# MS3-adapter.net
KiCad netlist of a schematic drawn in EAGLE
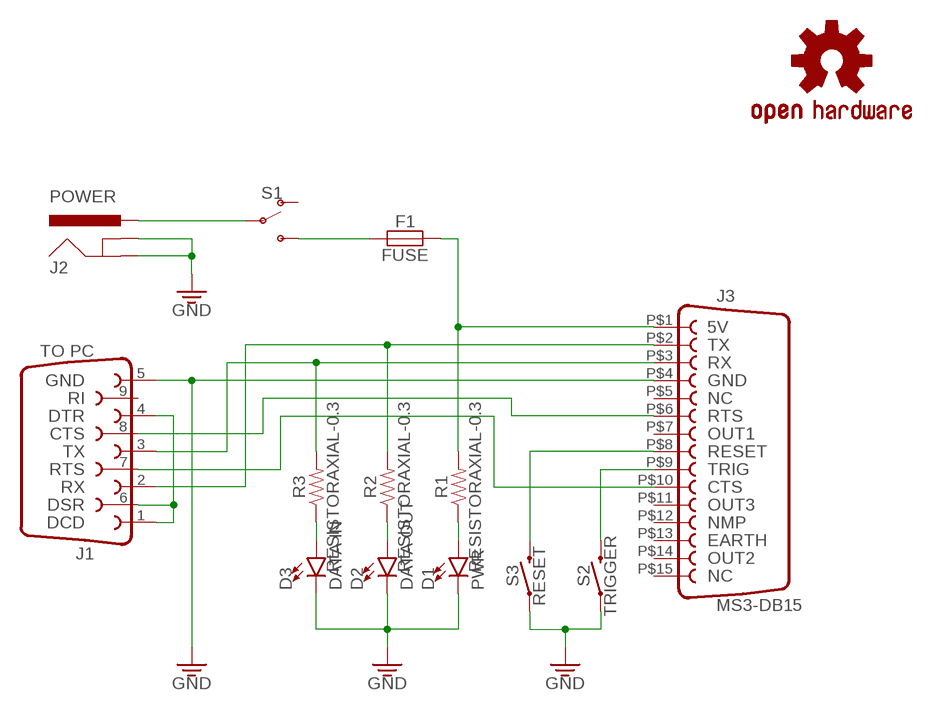
[diagram p0: schematic, sheet 1]

(export (version "E")
  (design (tool "Eeschema 10.0.6"))
  (components
    (comp (ref "D1")
      (value "PWR")
      (footprint "eagle-import:LED_5MM")
      (libsource (lib "eagle-import") (part "LED5MM"))
    )
    (comp (ref "D2")
      (value "DATA OUT")
      (footprint "eagle-import:LED_5MM")
      (libsource (lib "eagle-import") (part "LED5MM"))
    )
    (comp (ref "D3")
      (value "DATA IN")
      (footprint "eagle-import:LED_5MM")
      (libsource (lib "eagle-import") (part "LED5MM"))
    )
    (comp (ref "F1")
      (value "FUSE")
      (footprint "eagle-import:FUSEHOLDER-PAIR-5MM")
      (libsource (lib "eagle-import") (part "FUSE"))
    )
    (comp (ref "J1")
      (value "TO PC")
      (footprint "eagle-import:DB9-FEMALE")
      (libsource (lib "eagle-import") (part "DB9FEMALE"))
    )
    (comp (ref "J2")
      (value "POWER")
      (footprint "eagle-import:POWER_JACK_PTH")
      (libsource (lib "eagle-import") (part "POWER_JACK"))
    )
    (comp (ref "J3")
      (value "MS3-DB15")
      (footprint "eagle-import:DB15-MALE")
      (libsource (lib "eagle-import") (part "MS3-DB15"))
    )
    (comp (ref "LOGO1")
      (value "OSHW-LOGOS")
      (footprint "eagle-import:OSHW-LOGO-S")
      (libsource (lib "eagle-import") (part "OSHW-LOGOS"))
    )
    (comp (ref "R1")
      (value "RESISTORAXIAL-0.3")
      (footprint "eagle-import:AXIAL-0.3")
      (libsource (lib "eagle-import") (part "RESISTORAXIAL-0.3"))
    )
    (comp (ref "R2")
      (value "RESISTORAXIAL-0.3")
      (footprint "eagle-import:AXIAL-0.3")
      (libsource (lib "eagle-import") (part "RESISTORAXIAL-0.3"))
    )
    (comp (ref "R3")
      (value "RESISTORAXIAL-0.3")
      (footprint "eagle-import:AXIAL-0.3")
      (libsource (lib "eagle-import") (part "RESISTORAXIAL-0.3"))
    )
    (comp (ref "S1")
      (value "SWITCH-SPDT-PTH-11.6X4.0MM")
      (footprint "eagle-import:SWITCH_SPDT_PTH_11.6X4.0MM")
      (libsource (lib "eagle-import") (part "SWITCH-SPDT-PTH-11.6X4.0MM"))
    )
    (comp (ref "S2")
      (value "TRIGGER")
      (footprint "eagle-import:TACTILE_SWITCH_PTH_12MM")
      (libsource (lib "eagle-import") (part "MOMENTARY-SWITCH-SPST-PTH-12MM"))
    )
    (comp (ref "S3")
      (value "RESET")
      (footprint "eagle-import:TACTILE_SWITCH_PTH_12MM")
      (libsource (lib "eagle-import") (part "MOMENTARY-SWITCH-SPST-PTH-12MM"))
    )
  )
  (nets
    (net (code "1") (name "GND") (class "Default")
      (node (ref "D1") (pin "K") (pinfunction "C_K") (pintype "passive"))
      (node (ref "D2") (pin "K") (pinfunction "C_K") (pintype "passive"))
      (node (ref "D3") (pin "K") (pinfunction "C_K") (pintype "passive"))
      (node (ref "J1") (pin "5") (pinfunction "5_5") (pintype "passive"))
      (node (ref "J2") (pin "GND") (pinfunction "GND_GND") (pintype "bidirectional"))
      (node (ref "J2") (pin "GNDBREAK") (pinfunction "GNDBREAK_GNDBREAK") (pintype "bidirectional"))
      (node (ref "J3") (pin "P$4") (pinfunction "4_P$4") (pintype "passive"))
      (node (ref "S2") (pin "1") (pinfunction "1_1") (pintype "passive"))
      (node (ref "S3") (pin "1") (pinfunction "1_1") (pintype "passive"))
    )
    (net (code "2") (name "Net-(J1-Pad1)") (class "Default")
      (node (ref "J1") (pin "1") (pinfunction "1_1") (pintype "passive"))
      (node (ref "J1") (pin "4") (pinfunction "4_4") (pintype "passive"))
      (node (ref "J1") (pin "6") (pinfunction "6_6") (pintype "passive"))
    )
    (net (code "3") (name "Net-(J3-1)") (class "Default")
      (node (ref "F1") (pin "P$3") (pinfunction "2_P$3") (pintype "passive"))
      (node (ref "F1") (pin "P$4") (pinfunction "2_P$4") (pintype "passive"))
      (node (ref "J3") (pin "P$1") (pinfunction "1_P$1") (pintype "passive"))
      (node (ref "R1") (pin "P$2") (pinfunction "2_P$2") (pintype "passive"))
    )
    (net (code "4") (name "Net-(J3-2)") (class "Default")
      (node (ref "J1") (pin "2") (pinfunction "2_2") (pintype "passive"))
      (node (ref "J3") (pin "P$2") (pinfunction "2_P$2") (pintype "passive"))
      (node (ref "R2") (pin "P$2") (pinfunction "2_P$2") (pintype "passive"))
    )
    (net (code "5") (name "Net-(J3-3)") (class "Default")
      (node (ref "J1") (pin "3") (pinfunction "3_3") (pintype "passive"))
      (node (ref "J3") (pin "P$3") (pinfunction "3_P$3") (pintype "passive"))
      (node (ref "R3") (pin "P$2") (pinfunction "2_P$2") (pintype "passive"))
    )
    (net (code "6") (name "Net-(J3-6)") (class "Default")
      (node (ref "J1") (pin "8") (pinfunction "8_8") (pintype "passive"))
      (node (ref "J3") (pin "P$6") (pinfunction "6_P$6") (pintype "passive"))
    )
    (net (code "7") (name "Net-(J3-8)") (class "Default")
      (node (ref "J3") (pin "P$8") (pinfunction "8_P$8") (pintype "passive"))
      (node (ref "S3") (pin "3") (pinfunction "2_3") (pintype "passive"))
    )
    (net (code "8") (name "Net-(J3-9)") (class "Default")
      (node (ref "J3") (pin "P$9") (pinfunction "9_P$9") (pintype "passive"))
      (node (ref "S2") (pin "3") (pinfunction "2_3") (pintype "passive"))
    )
    (net (code "9") (name "Net-(J3-10)") (class "Default")
      (node (ref "J1") (pin "7") (pinfunction "7_7") (pintype "passive"))
      (node (ref "J3") (pin "P$10") (pinfunction "10_P$10") (pintype "passive"))
    )
    (net (code "10") (name "Net-(R1-1)") (class "Default")
      (node (ref "D1") (pin "A") (pinfunction "A_A") (pintype "passive"))
      (node (ref "R1") (pin "P$1") (pinfunction "1_P$1") (pintype "passive"))
    )
    (net (code "11") (name "Net-(R2-1)") (class "Default")
      (node (ref "D2") (pin "A") (pinfunction "A_A") (pintype "passive"))
      (node (ref "R2") (pin "P$1") (pinfunction "1_P$1") (pintype "passive"))
    )
    (net (code "12") (name "Net-(R3-1)") (class "Default")
      (node (ref "D3") (pin "A") (pinfunction "A_A") (pintype "passive"))
      (node (ref "R3") (pin "P$1") (pinfunction "1_P$1") (pintype "passive"))
    )
    (net (code "13") (name "Net-(S1-P)") (class "Default")
      (node (ref "J2") (pin "PWR") (pinfunction "PWR_PWR") (pintype "bidirectional"))
      (node (ref "S1") (pin "2") (pinfunction "P_2") (pintype "passive"))
    )
    (net (code "14") (name "Net-(S1-S)") (class "Default")
      (node (ref "F1") (pin "P$1") (pinfunction "1_P$1") (pintype "passive"))
      (node (ref "F1") (pin "P$2") (pinfunction "1_P$2") (pintype "passive"))
      (node (ref "S1") (pin "3") (pinfunction "S_3") (pintype "passive"))
    )
    (net (code "15") (name "unconnected-(J1-Pad9)") (class "Default")
      (node (ref "J1") (pin "9") (pinfunction "9_9") (pintype "passive"))
    )
    (net (code "16") (name "unconnected-(J3-5-PadP$5)") (class "Default")
      (node (ref "J3") (pin "P$5") (pinfunction "5_P$5") (pintype "passive"))
    )
    (net (code "17") (name "unconnected-(J3-7-PadP$7)") (class "Default")
      (node (ref "J3") (pin "P$7") (pinfunction "7_P$7") (pintype "passive"))
    )
    (net (code "18") (name "unconnected-(J3-11-PadP$11)") (class "Default")
      (node (ref "J3") (pin "P$11") (pinfunction "11_P$11") (pintype "passive"))
    )
    (net (code "19") (name "unconnected-(J3-12-PadP$12)") (class "Default")
      (node (ref "J3") (pin "P$12") (pinfunction "12_P$12") (pintype "passive"))
    )
    (net (code "20") (name "unconnected-(J3-13-PadP$13)") (class "Default")
      (node (ref "J3") (pin "P$13") (pinfunction "13_P$13") (pintype "passive"))
    )
    (net (code "21") (name "unconnected-(J3-14-PadP$14)") (class "Default")
      (node (ref "J3") (pin "P$14") (pinfunction "14_P$14") (pintype "passive"))
    )
    (net (code "22") (name "unconnected-(J3-15-PadP$15)") (class "Default")
      (node (ref "J3") (pin "P$15") (pinfunction "15_P$15") (pintype "passive"))
    )
    (net (code "23") (name "unconnected-(S1-O-Pad1)") (class "Default")
      (node (ref "S1") (pin "1") (pinfunction "O_1") (pintype "passive"))
    )
  )
)
